# mainboard.net
KiCad netlist of a schematic drawn in EAGLE
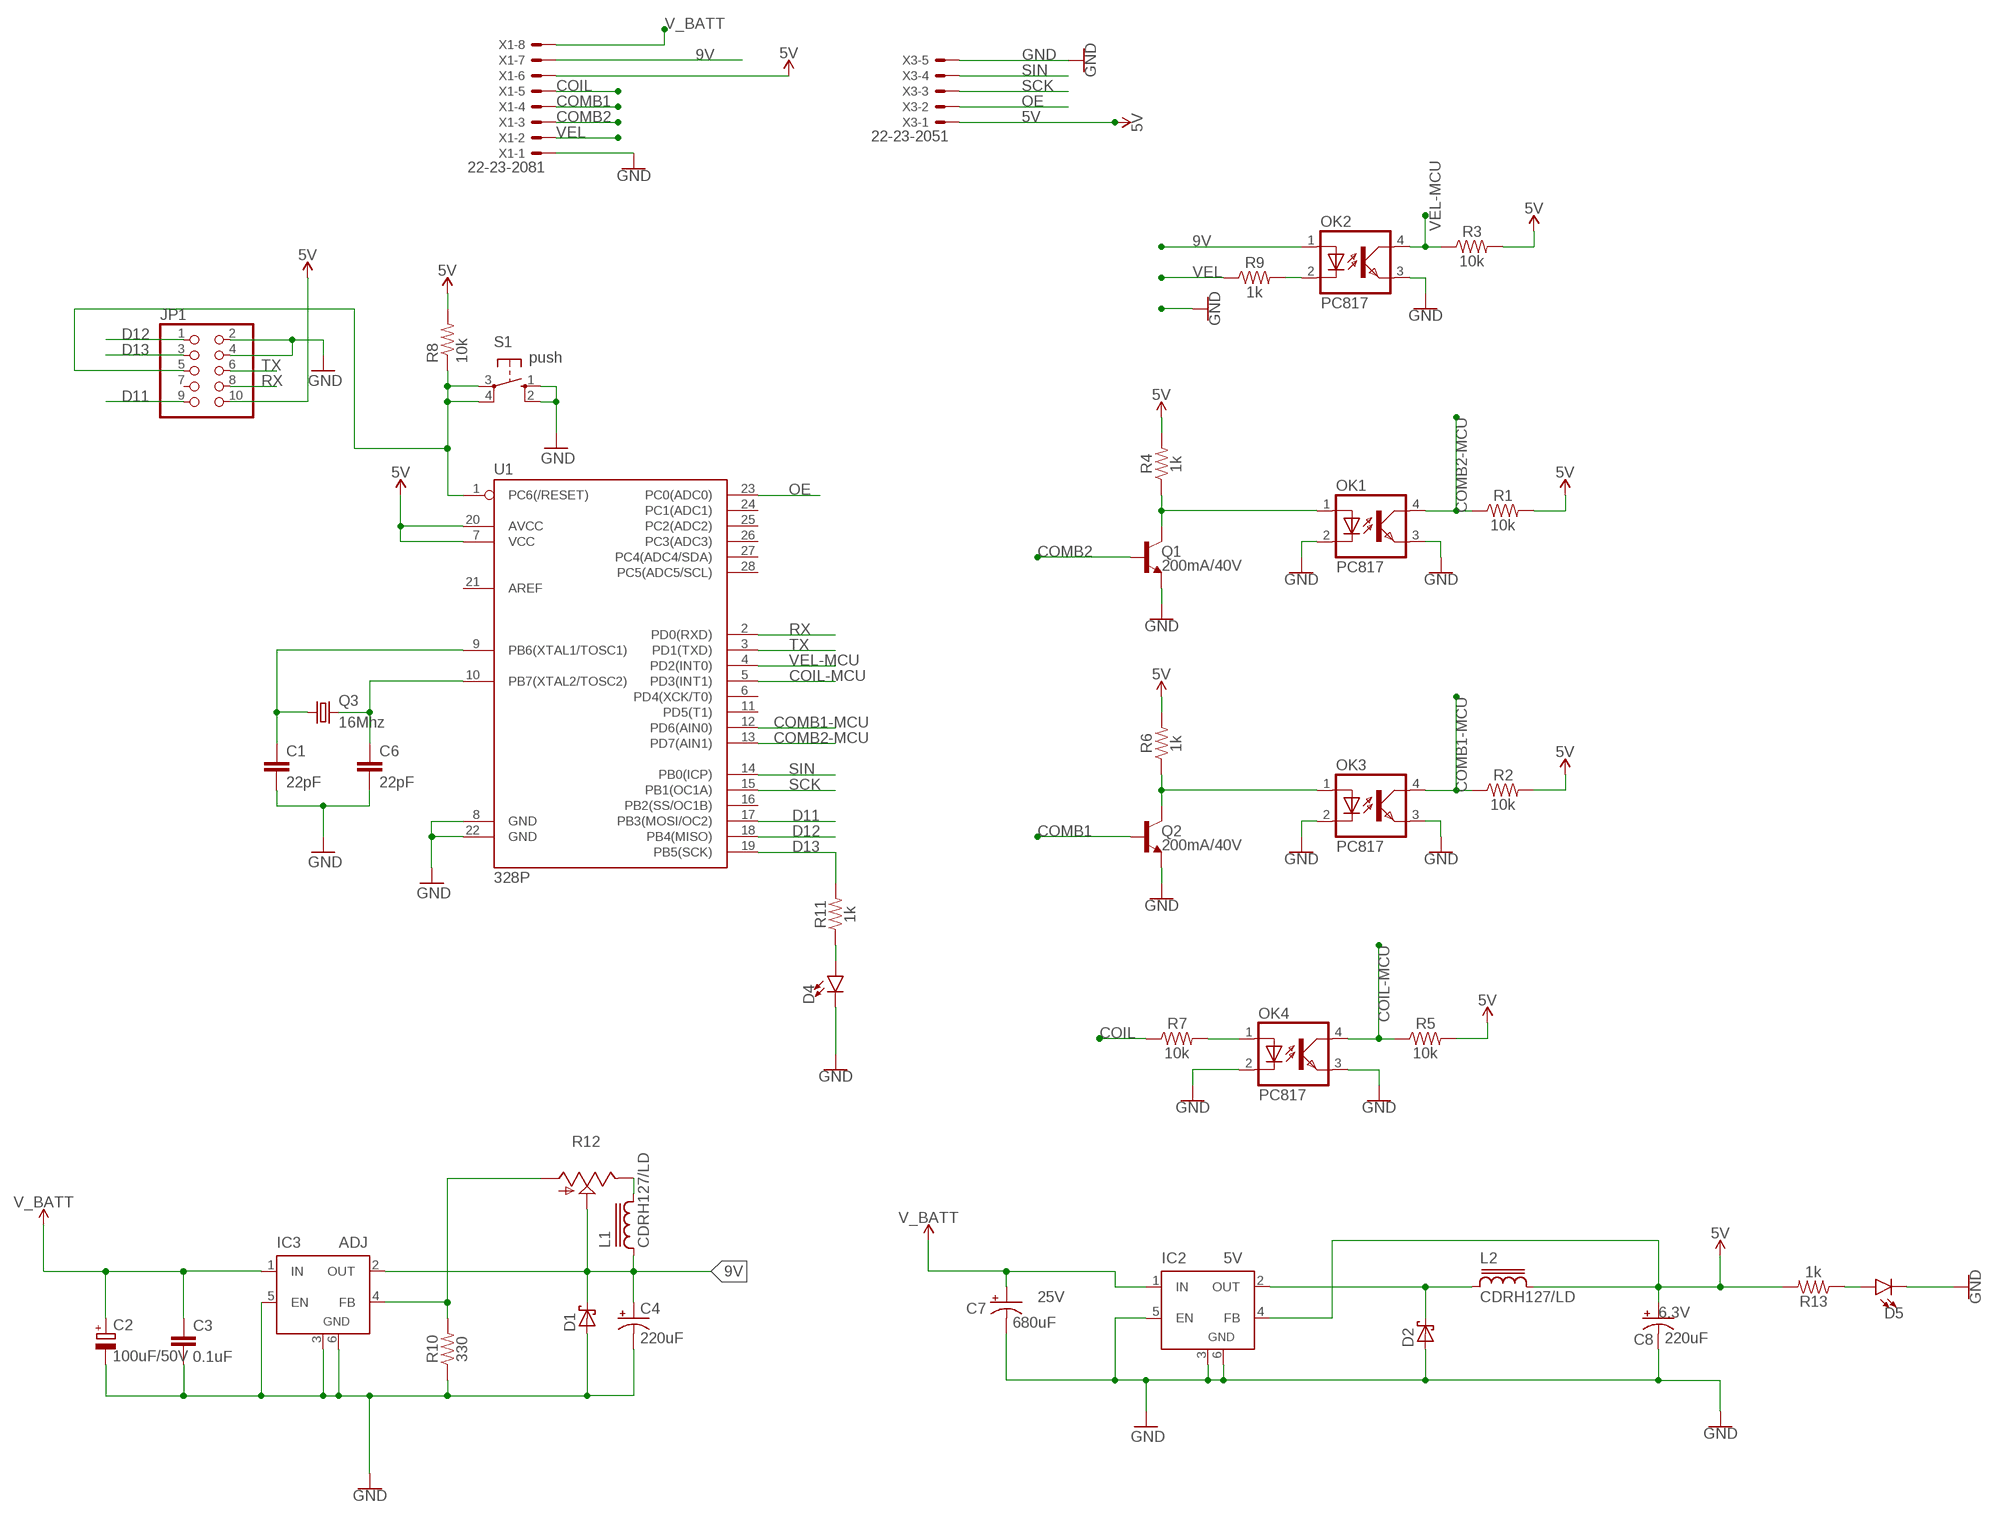
[diagram p0: schematic, sheet 1]

(export (version "E")
  (design (tool "Eeschema 10.0.6"))
  (components
    (comp (ref "C1")
      (value "22pF")
      (footprint "eagle-import:CAP-PTH-2.54")
      (libsource (lib "eagle-import") (part "22PF-PTH-2.54MM-200V-5%"))
    )
    (comp (ref "C2")
      (value "100uF/50V")
      (footprint "eagle-import:E3,5-8")
      (libsource (lib "eagle-import") (part "CPOL-EUE3.5-8"))
    )
    (comp (ref "C3")
      (value "0.1uF")
      (footprint "eagle-import:0603")
      (libsource (lib "eagle-import") (part "0.1UF-0603-25V-5%"))
    )
    (comp (ref "C4")
      (value "220uF")
      (footprint "eagle-import:UD-6,3X5,8_NICHICON")
      (libsource (lib "eagle-import") (part "rcl_334_CPOL-USUD-6,3X5,8"))
    )
    (comp (ref "C6")
      (value "22pF")
      (footprint "eagle-import:CAP-PTH-2.54")
      (libsource (lib "eagle-import") (part "22PF-PTH-2.54MM-200V-5%"))
    )
    (comp (ref "C7")
      (value "680uF")
      (footprint "eagle-import:E5-10,5")
      (fields (field (name "VOLTAGE") "25V"))
      (libsource (lib "eagle-import") (part "CPOL-USE5-10.5"))
    )
    (comp (ref "C8")
      (value "220uF")
      (footprint "eagle-import:UD-6,3X5,8_NICHICON")
      (fields (field (name "VOLTAGE") "6.3V"))
      (libsource (lib "eagle-import") (part "CPOL-USUD-6,3X5,8"))
    )
    (comp (ref "D1")
      (value "SCHOTTKY-DIODESMD")
      (footprint "eagle-import:SMB")
      (libsource (lib "eagle-import") (part "diode_210_SCHOTTKY-DIODESMD"))
    )
    (comp (ref "D2")
      (value "SCHOTTKY-DIODESMD")
      (footprint "eagle-import:SMB")
      (libsource (lib "eagle-import") (part "SCHOTTKY-DIODESMD"))
    )
    (comp (ref "D4")
      (value "LED3MM")
      (footprint "eagle-import:LED_3MM")
      (libsource (lib "eagle-import") (part "LED3MM"))
    )
    (comp (ref "D5")
      (value "LED3MM")
      (footprint "eagle-import:LED_3MM")
      (libsource (lib "eagle-import") (part "LED3MM"))
    )
    (comp (ref "IC2")
      (value "5V")
      (footprint "eagle-import:TO263-5")
      (libsource (lib "eagle-import") (part "LM2596S"))
    )
    (comp (ref "IC3")
      (value "ADJ")
      (footprint "eagle-import:TO263-5")
      (libsource (lib "eagle-import") (part "LM2596S"))
    )
    (comp (ref "JP1")
      (value "PINHD-2X5")
      (footprint "eagle-import:2X05")
      (libsource (lib "eagle-import") (part "PINHD-2X5"))
    )
    (comp (ref "L1")
      (value "CDRH127/LD")
      (footprint "eagle-import:CDRH127_LD")
      (libsource (lib "eagle-import") (part "CDRH127/LD"))
    )
    (comp (ref "L2")
      (value "CDRH127/LD")
      (footprint "eagle-import:CDRH127_LD")
      (libsource (lib "eagle-import") (part "CDRH127/LD"))
    )
    (comp (ref "OK1")
      (value "PC817")
      (footprint "eagle-import:DIL04")
      (fields (field (name "MPN") "PC817X4J000F"))
      (libsource (lib "eagle-import") (part "PC817"))
    )
    (comp (ref "OK2")
      (value "PC817")
      (footprint "eagle-import:DIL04")
      (fields (field (name "MPN") "PC817X4J000F"))
      (libsource (lib "eagle-import") (part "PC817"))
    )
    (comp (ref "OK3")
      (value "PC817")
      (footprint "eagle-import:DIL04")
      (fields (field (name "MPN") "PC817X4J000F"))
      (libsource (lib "eagle-import") (part "PC817"))
    )
    (comp (ref "OK4")
      (value "PC817")
      (footprint "eagle-import:DIL04")
      (fields (field (name "MPN") "PC817X4J000F"))
      (libsource (lib "eagle-import") (part "PC817"))
    )
    (comp (ref "Q1")
      (value "200mA/40V")
      (footprint "eagle-import:TO-92")
      (libsource (lib "eagle-import") (part "TRANS_NPN-2N3904"))
    )
    (comp (ref "Q2")
      (value "200mA/40V")
      (footprint "eagle-import:TO-92")
      (libsource (lib "eagle-import") (part "TRANS_NPN-2N3904"))
    )
    (comp (ref "Q3")
      (value "16Mhz")
      (footprint "eagle-import:HC49U-V")
      (libsource (lib "eagle-import") (part "CRYSTALHC49U-V"))
    )
    (comp (ref "R1")
      (value "10k")
      (footprint "eagle-import:AXIAL-0.3")
      (libsource (lib "eagle-import") (part "10KOHM-HORIZ-1/4W-5%"))
    )
    (comp (ref "R2")
      (value "10k")
      (footprint "eagle-import:AXIAL-0.3")
      (libsource (lib "eagle-import") (part "10KOHM-HORIZ-1/4W-5%"))
    )
    (comp (ref "R3")
      (value "10k")
      (footprint "eagle-import:AXIAL-0.3")
      (libsource (lib "eagle-import") (part "10KOHM-HORIZ-1/4W-5%"))
    )
    (comp (ref "R4")
      (value "1k")
      (footprint "eagle-import:AXIAL-0.3")
      (libsource (lib "eagle-import") (part "1KOHM-HORIZ-1/4W-5%"))
    )
    (comp (ref "R5")
      (value "10k")
      (footprint "eagle-import:AXIAL-0.3")
      (libsource (lib "eagle-import") (part "10KOHM-HORIZ-1/4W-5%"))
    )
    (comp (ref "R6")
      (value "1k")
      (footprint "eagle-import:AXIAL-0.3")
      (libsource (lib "eagle-import") (part "1KOHM-HORIZ-1/4W-5%"))
    )
    (comp (ref "R7")
      (value "10k")
      (footprint "eagle-import:AXIAL-0.3")
      (libsource (lib "eagle-import") (part "10KOHM-HORIZ-1/4W-5%"))
    )
    (comp (ref "R8")
      (value "10k")
      (footprint "eagle-import:AXIAL-0.3")
      (libsource (lib "eagle-import") (part "SparkFun-Resistors_532_10KOHM-HORIZ-1/4W-5%"))
    )
    (comp (ref "R9")
      (value "1k")
      (footprint "eagle-import:AXIAL-0.3")
      (libsource (lib "eagle-import") (part "1KOHM-HORIZ-1/4W-5%"))
    )
    (comp (ref "R10")
      (value "330")
      (footprint "eagle-import:AXIAL-0.3")
      (libsource (lib "eagle-import") (part "1KOHM-HORIZ-1/4W-5%"))
    )
    (comp (ref "R11")
      (value "1k")
      (footprint "eagle-import:AXIAL-0.3")
      (libsource (lib "eagle-import") (part "1KOHM-HORIZ-1/4W-5%"))
    )
    (comp (ref "R12")
      (value "TRIM_US-S64W")
      (footprint "eagle-import:S64W")
      (libsource (lib "eagle-import") (part "TRIM_US-S64W"))
    )
    (comp (ref "R13")
      (value "1k")
      (footprint "eagle-import:AXIAL-0.3")
      (libsource (lib "eagle-import") (part "1KOHM-HORIZ-1/4W-5%"))
    )
    (comp (ref "S1")
      (value "push")
      (footprint "eagle-import:B3F-10XX")
      (fields (field (name "MPN") "B3F-1000"))
      (libsource (lib "eagle-import") (part "10-XX"))
    )
    (comp (ref "U1")
      (value "328P")
      (footprint "eagle-import:DIP28")
      (libsource (lib "eagle-import") (part "ATMEGA328P_PDIP"))
    )
    (comp (ref "X1")
      (value "22-23-2081")
      (footprint "eagle-import:22-23-2081")
      (fields (field (name "MF") "MOLEX"))
      (libsource (lib "eagle-import") (part "22-23-2081"))
    )
    (comp (ref "X3")
      (value "22-23-2051")
      (footprint "eagle-import:22-23-2051")
      (fields (field (name "MF") "MOLEX"))
      (libsource (lib "eagle-import") (part "22-23-2051"))
    )
  )
  (nets
    (net (code "1") (name "/COIL") (class "Default")
      (node (ref "R7") (pin "P$1") (pinfunction "1_P$1") (pintype "passive"))
      (node (ref "X1") (pin "5") (pinfunction "S_5") (pintype "passive"))
    )
    (net (code "2") (name "/COIL-MCU") (class "Default")
      (node (ref "OK4") (pin "4") (pinfunction "COL_4") (pintype "passive"))
      (node (ref "R5") (pin "P$1") (pinfunction "1_P$1") (pintype "passive"))
      (node (ref "U1") (pin "5") (pinfunction "PD3(INT1)_5") (pintype "bidirectional"))
    )
    (net (code "3") (name "/COMB1") (class "Default")
      (node (ref "Q2") (pin "2") (pinfunction "B_2") (pintype "passive"))
      (node (ref "X1") (pin "4") (pinfunction "S_4") (pintype "passive"))
    )
    (net (code "4") (name "/COMB1-MCU") (class "Default")
      (node (ref "OK3") (pin "4") (pinfunction "COL_4") (pintype "passive"))
      (node (ref "R2") (pin "P$1") (pinfunction "1_P$1") (pintype "passive"))
      (node (ref "U1") (pin "12") (pinfunction "PD6(AIN0)_12") (pintype "bidirectional"))
    )
    (net (code "5") (name "/COMB2") (class "Default")
      (node (ref "Q1") (pin "2") (pinfunction "B_2") (pintype "passive"))
      (node (ref "X1") (pin "3") (pinfunction "S_3") (pintype "passive"))
    )
    (net (code "6") (name "/COMB2-MCU") (class "Default")
      (node (ref "OK1") (pin "4") (pinfunction "COL_4") (pintype "passive"))
      (node (ref "R1") (pin "P$1") (pinfunction "1_P$1") (pintype "passive"))
      (node (ref "U1") (pin "13") (pinfunction "PD7(AIN1)_13") (pintype "bidirectional"))
    )
    (net (code "7") (name "/D11") (class "Default")
      (node (ref "JP1") (pin "9") (pinfunction "9_9") (pintype "passive"))
      (node (ref "U1") (pin "17") (pinfunction "PB3(MOSI/OC2)_17") (pintype "bidirectional"))
    )
    (net (code "8") (name "/D12") (class "Default")
      (node (ref "JP1") (pin "1") (pinfunction "1_1") (pintype "passive"))
      (node (ref "U1") (pin "18") (pinfunction "PB4(MISO)_18") (pintype "bidirectional"))
    )
    (net (code "9") (name "/D13") (class "Default")
      (node (ref "JP1") (pin "3") (pinfunction "3_3") (pintype "passive"))
      (node (ref "R11") (pin "P$2") (pinfunction "2_P$2") (pintype "passive"))
      (node (ref "U1") (pin "19") (pinfunction "PB5(SCK)_19") (pintype "bidirectional"))
    )
    (net (code "10") (name "/OE") (class "Default")
      (node (ref "U1") (pin "23") (pinfunction "PC0(ADC0)_23") (pintype "bidirectional"))
      (node (ref "X3") (pin "2") (pinfunction "S_2") (pintype "passive"))
    )
    (net (code "11") (name "/RX") (class "Default")
      (node (ref "JP1") (pin "8") (pinfunction "8_8") (pintype "passive"))
      (node (ref "U1") (pin "2") (pinfunction "PD0(RXD)_2") (pintype "bidirectional"))
    )
    (net (code "12") (name "/SCK") (class "Default")
      (node (ref "U1") (pin "15") (pinfunction "PB1(OC1A)_15") (pintype "bidirectional"))
      (node (ref "X3") (pin "3") (pinfunction "S_3") (pintype "passive"))
    )
    (net (code "13") (name "/SIN") (class "Default")
      (node (ref "U1") (pin "14") (pinfunction "PB0(ICP)_14") (pintype "bidirectional"))
      (node (ref "X3") (pin "4") (pinfunction "S_4") (pintype "passive"))
    )
    (net (code "14") (name "/TX") (class "Default")
      (node (ref "JP1") (pin "6") (pinfunction "6_6") (pintype "passive"))
      (node (ref "U1") (pin "3") (pinfunction "PD1(TXD)_3") (pintype "bidirectional"))
    )
    (net (code "15") (name "/VEL") (class "Default")
      (node (ref "R9") (pin "P$1") (pinfunction "1_P$1") (pintype "passive"))
      (node (ref "X1") (pin "2") (pinfunction "S_2") (pintype "passive"))
    )
    (net (code "16") (name "/VEL-MCU") (class "Default")
      (node (ref "OK2") (pin "4") (pinfunction "COL_4") (pintype "passive"))
      (node (ref "R3") (pin "P$1") (pinfunction "1_P$1") (pintype "passive"))
      (node (ref "U1") (pin "4") (pinfunction "PD2(INT0)_4") (pintype "bidirectional"))
    )
    (net (code "17") (name "5V") (class "Default")
      (node (ref "C8") (pin "+") (pinfunction "+_+") (pintype "passive"))
      (node (ref "IC2") (pin "4") (pinfunction "FB_4") (pintype "input"))
      (node (ref "JP1") (pin "10") (pinfunction "10_10") (pintype "passive"))
      (node (ref "L2") (pin "2") (pinfunction "2_2") (pintype "passive"))
      (node (ref "R1") (pin "P$2") (pinfunction "2_P$2") (pintype "passive"))
      (node (ref "R13") (pin "P$2") (pinfunction "2_P$2") (pintype "passive"))
      (node (ref "R2") (pin "P$2") (pinfunction "2_P$2") (pintype "passive"))
      (node (ref "R3") (pin "P$2") (pinfunction "2_P$2") (pintype "passive"))
      (node (ref "R4") (pin "P$2") (pinfunction "2_P$2") (pintype "passive"))
      (node (ref "R5") (pin "P$2") (pinfunction "2_P$2") (pintype "passive"))
      (node (ref "R6") (pin "P$2") (pinfunction "2_P$2") (pintype "passive"))
      (node (ref "R8") (pin "P$2") (pinfunction "2_P$2") (pintype "passive"))
      (node (ref "U1") (pin "20") (pinfunction "AVCC_20") (pintype "bidirectional"))
      (node (ref "U1") (pin "7") (pinfunction "VCC_7") (pintype "bidirectional"))
      (node (ref "X1") (pin "6") (pinfunction "S_6") (pintype "passive"))
      (node (ref "X3") (pin "1") (pinfunction "S_1") (pintype "passive"))
    )
    (net (code "18") (name "9V") (class "Default")
      (node (ref "C4") (pin "+") (pinfunction "+_+") (pintype "passive"))
      (node (ref "D1") (pin "C") (pinfunction "C_C") (pintype "passive"))
      (node (ref "IC3") (pin "2") (pinfunction "OUT_2") (pintype "output"))
      (node (ref "L1") (pin "1") (pinfunction "1_1") (pintype "passive"))
      (node (ref "OK2") (pin "1") (pinfunction "A_1") (pintype "passive"))
      (node (ref "R12") (pin "S") (pinfunction "S_S") (pintype "passive"))
      (node (ref "X1") (pin "7") (pinfunction "S_7") (pintype "passive"))
    )
    (net (code "19") (name "GND") (class "Default")
      (node (ref "C1") (pin "2") (pinfunction "2_2") (pintype "passive"))
      (node (ref "C2") (pin "-") (pinfunction "-_-") (pintype "passive"))
      (node (ref "C3") (pin "2") (pinfunction "2_2") (pintype "passive"))
      (node (ref "C4") (pin "-") (pinfunction "-_-") (pintype "passive"))
      (node (ref "C6") (pin "2") (pinfunction "2_2") (pintype "passive"))
      (node (ref "C7") (pin "-") (pinfunction "-_-") (pintype "passive"))
      (node (ref "C8") (pin "-") (pinfunction "-_-") (pintype "passive"))
      (node (ref "D1") (pin "A") (pinfunction "A_A") (pintype "passive"))
      (node (ref "D2") (pin "A") (pinfunction "A_A") (pintype "passive"))
      (node (ref "D4") (pin "K") (pinfunction "C_K") (pintype "passive"))
      (node (ref "D5") (pin "K") (pinfunction "C_K") (pintype "passive"))
      (node (ref "IC2") (pin "3") (pinfunction "GND_3") (pintype "power_in"))
      (node (ref "IC2") (pin "5") (pinfunction "EN_5") (pintype "input"))
      (node (ref "IC2") (pin "6") (pinfunction "GND_6") (pintype "power_in"))
      (node (ref "IC3") (pin "3") (pinfunction "GND_3") (pintype "power_in"))
      (node (ref "IC3") (pin "5") (pinfunction "EN_5") (pintype "input"))
      (node (ref "IC3") (pin "6") (pinfunction "GND_6") (pintype "power_in"))
      (node (ref "JP1") (pin "2") (pinfunction "2_2") (pintype "passive"))
      (node (ref "JP1") (pin "4") (pinfunction "4_4") (pintype "passive"))
      (node (ref "OK1") (pin "2") (pinfunction "C_2") (pintype "passive"))
      (node (ref "OK1") (pin "3") (pinfunction "EMIT_3") (pintype "passive"))
      (node (ref "OK2") (pin "3") (pinfunction "EMIT_3") (pintype "passive"))
      (node (ref "OK3") (pin "2") (pinfunction "C_2") (pintype "passive"))
      (node (ref "OK3") (pin "3") (pinfunction "EMIT_3") (pintype "passive"))
      (node (ref "OK4") (pin "2") (pinfunction "C_2") (pintype "passive"))
      (node (ref "OK4") (pin "3") (pinfunction "EMIT_3") (pintype "passive"))
      (node (ref "Q1") (pin "1") (pinfunction "E_1") (pintype "passive"))
      (node (ref "Q2") (pin "1") (pinfunction "E_1") (pintype "passive"))
      (node (ref "R10") (pin "P$1") (pinfunction "1_P$1") (pintype "passive"))
      (node (ref "S1") (pin "1") (pinfunction "S_1") (pintype "passive"))
      (node (ref "S1") (pin "2") (pinfunction "S1_2") (pintype "passive"))
      (node (ref "U1") (pin "22") (pinfunction "GND_22") (pintype "bidirectional"))
      (node (ref "U1") (pin "8") (pinfunction "GND_8") (pintype "bidirectional"))
      (node (ref "X1") (pin "1") (pinfunction "S_1") (pintype "passive"))
      (node (ref "X3") (pin "5") (pinfunction "S_5") (pintype "passive"))
    )
    (net (code "20") (name "Net-(IC2-OUT)") (class "Default")
      (node (ref "D2") (pin "C") (pinfunction "C_C") (pintype "passive"))
      (node (ref "IC2") (pin "2") (pinfunction "OUT_2") (pintype "output"))
      (node (ref "L2") (pin "1") (pinfunction "1_1") (pintype "passive"))
    )
    (net (code "21") (name "Net-(IC3-FB)") (class "Default")
      (node (ref "IC3") (pin "4") (pinfunction "FB_4") (pintype "input"))
      (node (ref "R10") (pin "P$2") (pinfunction "2_P$2") (pintype "passive"))
      (node (ref "R12") (pin "A") (pinfunction "A_A") (pintype "passive"))
    )
    (net (code "22") (name "Net-(L1-Pad2)") (class "Default")
      (node (ref "L1") (pin "2") (pinfunction "2_2") (pintype "passive"))
      (node (ref "R12") (pin "E") (pinfunction "E_E") (pintype "passive"))
    )
    (net (code "23") (name "Net-(OK1-A)") (class "Default")
      (node (ref "OK1") (pin "1") (pinfunction "A_1") (pintype "passive"))
      (node (ref "Q1") (pin "3") (pinfunction "C_3") (pintype "passive"))
      (node (ref "R4") (pin "P$1") (pinfunction "1_P$1") (pintype "passive"))
    )
    (net (code "24") (name "Net-(OK2-C)") (class "Default")
      (node (ref "OK2") (pin "2") (pinfunction "C_2") (pintype "passive"))
      (node (ref "R9") (pin "P$2") (pinfunction "2_P$2") (pintype "passive"))
    )
    (net (code "25") (name "Net-(OK3-A)") (class "Default")
      (node (ref "OK3") (pin "1") (pinfunction "A_1") (pintype "passive"))
      (node (ref "Q2") (pin "3") (pinfunction "C_3") (pintype "passive"))
      (node (ref "R6") (pin "P$1") (pinfunction "1_P$1") (pintype "passive"))
    )
    (net (code "26") (name "Net-(OK4-A)") (class "Default")
      (node (ref "OK4") (pin "1") (pinfunction "A_1") (pintype "passive"))
      (node (ref "R7") (pin "P$2") (pinfunction "2_P$2") (pintype "passive"))
    )
    (net (code "27") (name "Net-(R8-1)") (class "Default")
      (node (ref "JP1") (pin "5") (pinfunction "5_5") (pintype "passive"))
      (node (ref "R8") (pin "P$1") (pinfunction "1_P$1") (pintype "passive"))
      (node (ref "S1") (pin "3") (pinfunction "P_3") (pintype "passive"))
      (node (ref "S1") (pin "4") (pinfunction "P1_4") (pintype "passive"))
      (node (ref "U1") (pin "1") (pinfunction "PC6(/RESET)_1") (pintype "bidirectional"))
    )
    (net (code "28") (name "Net-(R11-1)") (class "Default")
      (node (ref "D4") (pin "A") (pinfunction "A_A") (pintype "passive"))
      (node (ref "R11") (pin "P$1") (pinfunction "1_P$1") (pintype "passive"))
    )
    (net (code "29") (name "Net-(R13-1)") (class "Default")
      (node (ref "D5") (pin "A") (pinfunction "A_A") (pintype "passive"))
      (node (ref "R13") (pin "P$1") (pinfunction "1_P$1") (pintype "passive"))
    )
    (net (code "30") (name "Net-(U1-PB6(XTAL1{slash}TOSC1))") (class "Default")
      (node (ref "C1") (pin "1") (pinfunction "1_1") (pintype "passive"))
      (node (ref "Q3") (pin "1") (pinfunction "1_1") (pintype "passive"))
      (node (ref "U1") (pin "9") (pinfunction "PB6(XTAL1/TOSC1)_9") (pintype "bidirectional"))
    )
    (net (code "31") (name "Net-(U1-PB7(XTAL2{slash}TOSC2))") (class "Default")
      (node (ref "C6") (pin "1") (pinfunction "1_1") (pintype "passive"))
      (node (ref "Q3") (pin "2") (pinfunction "2_2") (pintype "passive"))
      (node (ref "U1") (pin "10") (pinfunction "PB7(XTAL2/TOSC2)_10") (pintype "bidirectional"))
    )
    (net (code "32") (name "V_BATT") (class "Default")
      (node (ref "C2") (pin "+") (pinfunction "+_+") (pintype "passive"))
      (node (ref "C3") (pin "1") (pinfunction "1_1") (pintype "passive"))
      (node (ref "C7") (pin "+") (pinfunction "+_+") (pintype "passive"))
      (node (ref "IC2") (pin "1") (pinfunction "IN_1") (pintype "input"))
      (node (ref "IC3") (pin "1") (pinfunction "IN_1") (pintype "input"))
      (node (ref "X1") (pin "8") (pinfunction "S_8") (pintype "passive"))
    )
    (net (code "33") (name "unconnected-(JP1-Pad7)") (class "Default")
      (node (ref "JP1") (pin "7") (pinfunction "7_7") (pintype "passive"))
    )
    (net (code "34") (name "unconnected-(U1-AREF-Pad21)") (class "Default")
      (node (ref "U1") (pin "21") (pinfunction "AREF_21") (pintype "bidirectional"))
    )
    (net (code "35") (name "unconnected-(U1-PB2(SS{slash}OC1B)-Pad16)") (class "Default")
      (node (ref "U1") (pin "16") (pinfunction "PB2(SS/OC1B)_16") (pintype "bidirectional"))
    )
    (net (code "36") (name "unconnected-(U1-PC1(ADC1)-Pad24)") (class "Default")
      (node (ref "U1") (pin "24") (pinfunction "PC1(ADC1)_24") (pintype "bidirectional"))
    )
    (net (code "37") (name "unconnected-(U1-PC2(ADC2)-Pad25)") (class "Default")
      (node (ref "U1") (pin "25") (pinfunction "PC2(ADC2)_25") (pintype "bidirectional"))
    )
    (net (code "38") (name "unconnected-(U1-PC3(ADC3)-Pad26)") (class "Default")
      (node (ref "U1") (pin "26") (pinfunction "PC3(ADC3)_26") (pintype "bidirectional"))
    )
    (net (code "39") (name "unconnected-(U1-PC4(ADC4{slash}SDA)-Pad27)") (class "Default")
      (node (ref "U1") (pin "27") (pinfunction "PC4(ADC4/SDA)_27") (pintype "bidirectional"))
    )
    (net (code "40") (name "unconnected-(U1-PC5(ADC5{slash}SCL)-Pad28)") (class "Default")
      (node (ref "U1") (pin "28") (pinfunction "PC5(ADC5/SCL)_28") (pintype "bidirectional"))
    )
    (net (code "41") (name "unconnected-(U1-PD4(XCK{slash}T0)-Pad6)") (class "Default")
      (node (ref "U1") (pin "6") (pinfunction "PD4(XCK/T0)_6") (pintype "bidirectional"))
    )
    (net (code "42") (name "unconnected-(U1-PD5(T1)-Pad11)") (class "Default")
      (node (ref "U1") (pin "11") (pinfunction "PD5(T1)_11") (pintype "bidirectional"))
    )
  )
)
